# NearField_E_Probe.net
KiCad netlist of a schematic drawn in Altium Designer
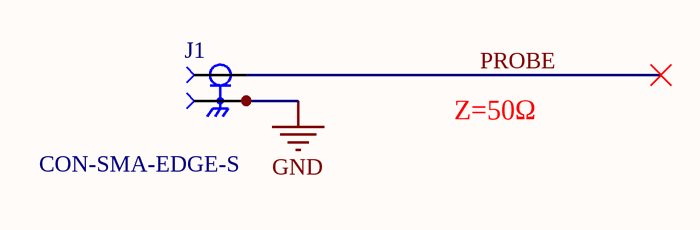
[diagram p0: NearField_E_Probe.SchDoc]

(export (version "E")
  (design (tool "Eeschema 10.0.6"))
  (components
    (comp (ref "J1")
      (value "CON-SMA-EDGE-S")
      (footprint "RFSOLUTIONS_CON-SMA-EDGE-S")
      (description "SMA Connector Jack, Female Socket - Board Edge, End Launch Solder")
      (fields (field (name "MF") "RF Solutions") (field (name "DIGI-KEY_PART_NUMBER") "CON-SMA-EDGE-S-ND"))
      (libsource (lib "E-Field-Near-Field Probe") (part "CON-SMA-EDGE-S"))
    )
  )
  (nets
    (net (code "1") (name "/PROBE") (class "Default")
      (node (ref "J1") (pin "1") (pinfunction "1_1") (pintype "passive+no_connect"))
    )
    (net (code "2") (name "GND") (class "Default")
      (node (ref "J1") (pin "G1") (pinfunction "2_G1") (pintype "passive"))
      (node (ref "J1") (pin "G2") (pinfunction "2_G2") (pintype "passive"))
      (node (ref "J1") (pin "G3") (pinfunction "2_G3") (pintype "passive"))
      (node (ref "J1") (pin "G4") (pinfunction "2_G4") (pintype "passive"))
    )
  )
)
